# F4_mini.net
KiCad netlist of a schematic drawn in EAGLE
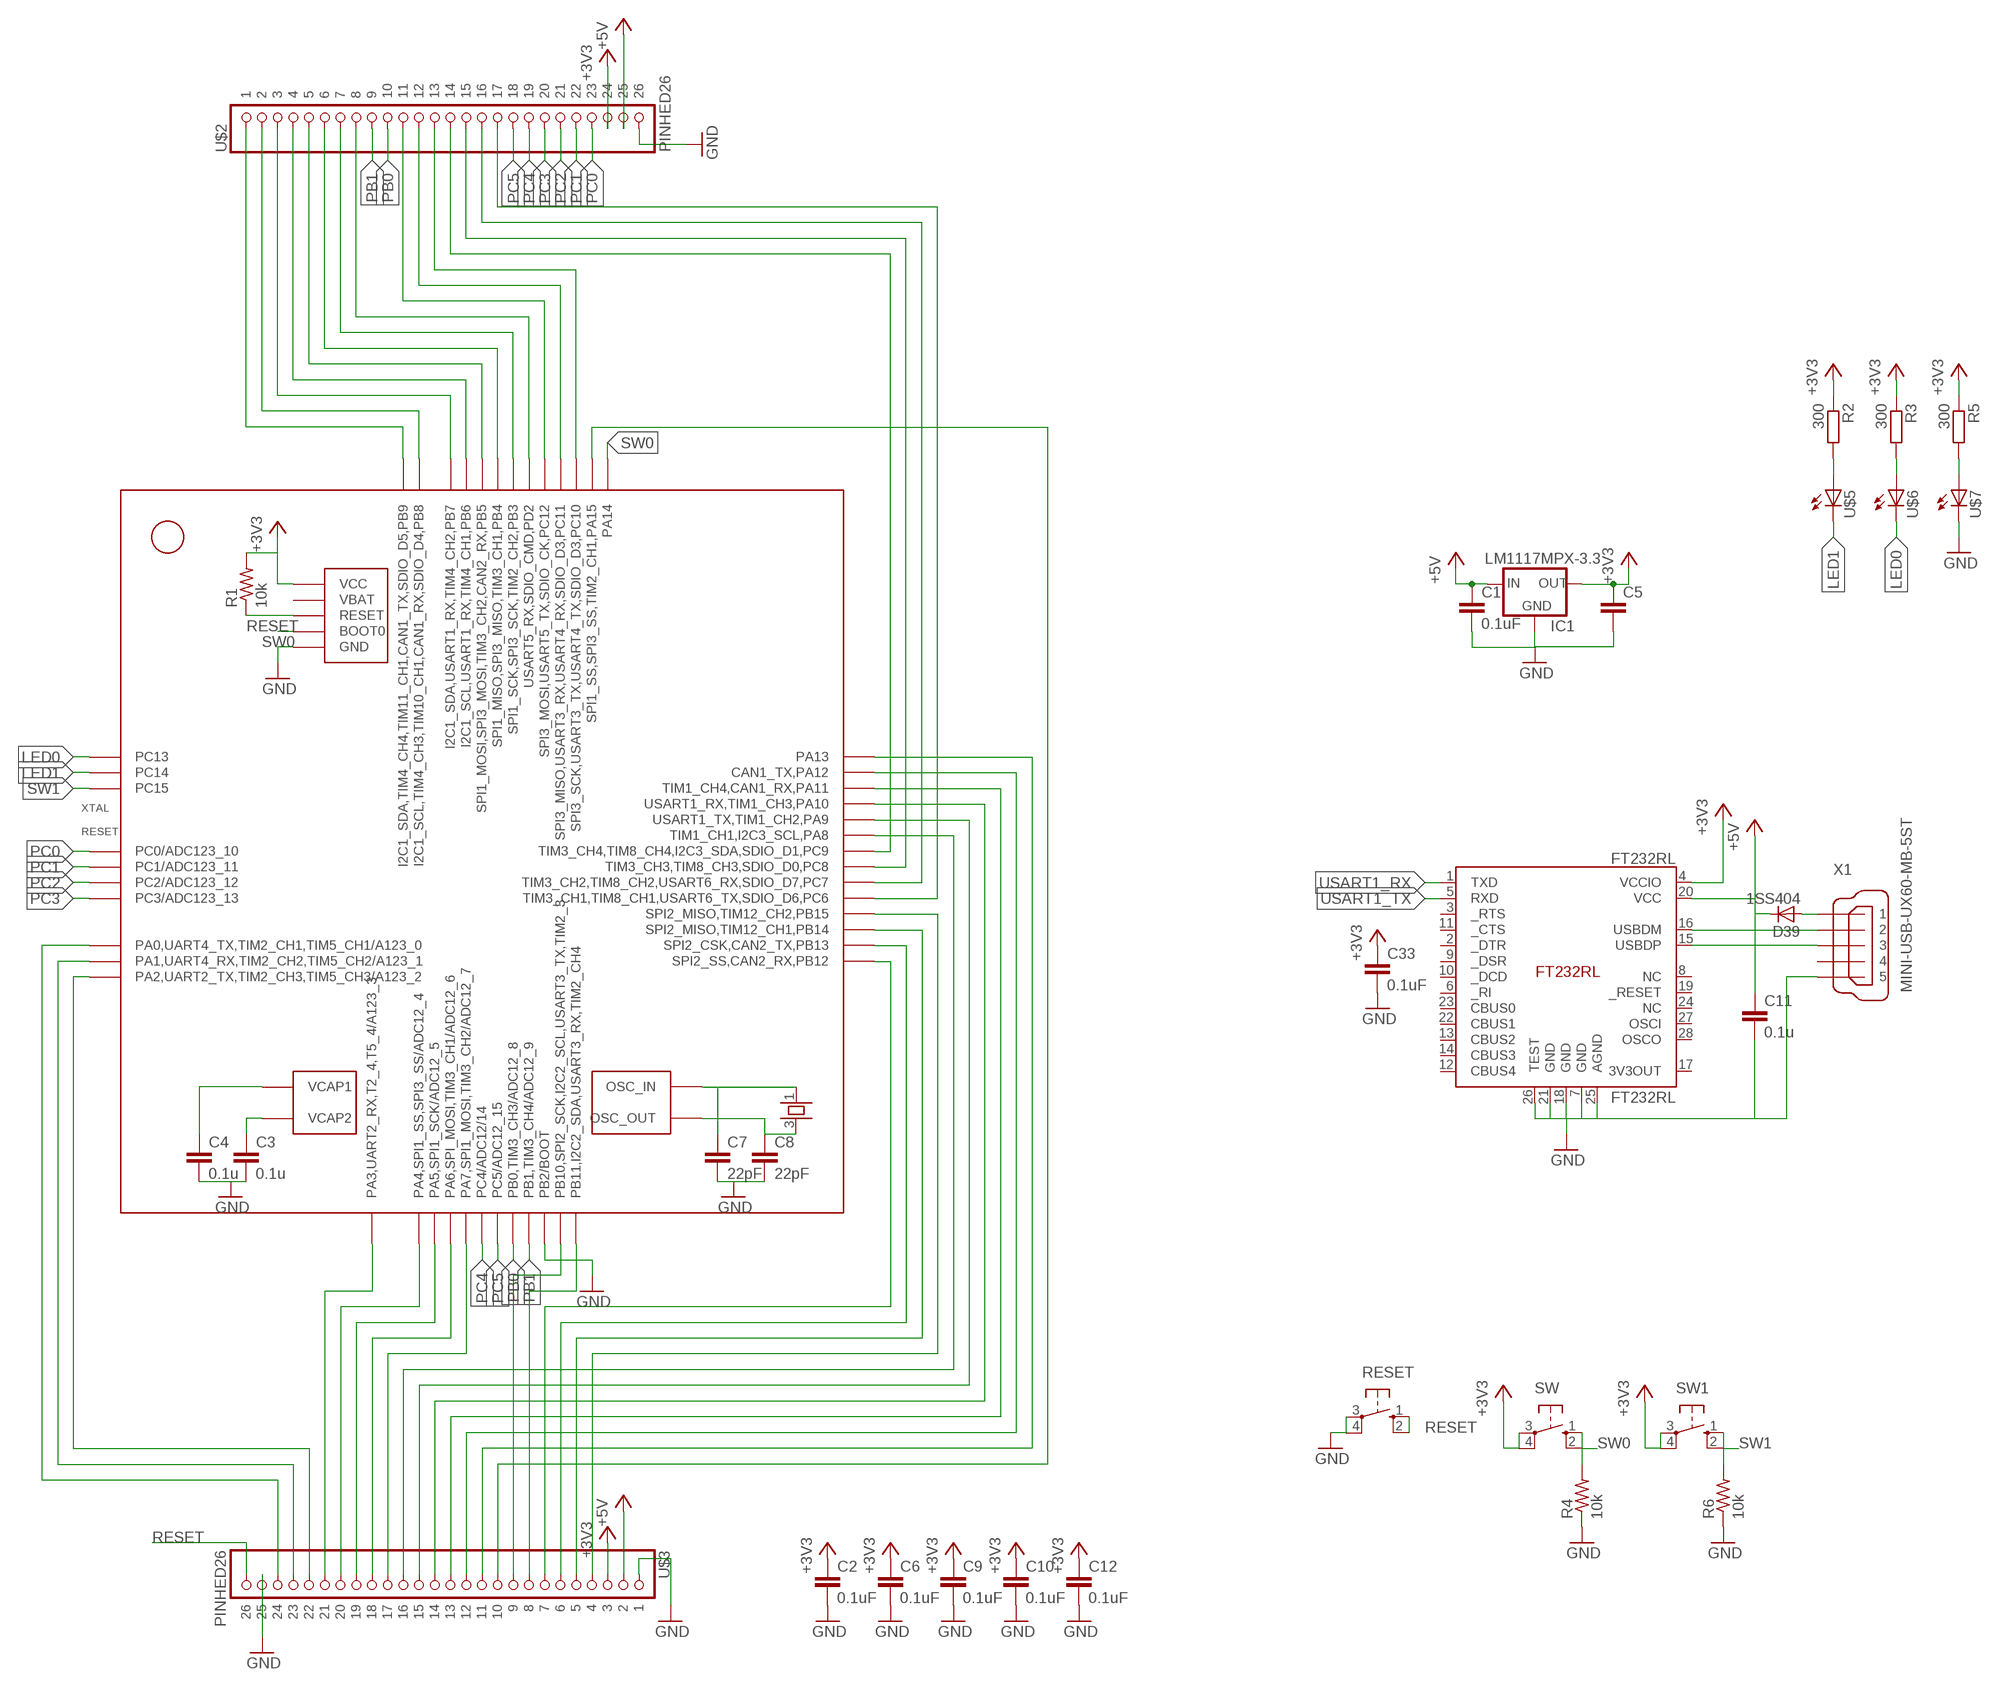
[diagram p0: schematic, sheet 1]

(export (version "E")
  (design (tool "Eeschema 10.0.6"))
  (components
    (comp (ref "C1")
      (value "0.1uF")
      (footprint "eagle-import:C0603K")
      (libsource (lib "eagle-import") (part "C-EUC0603K"))
    )
    (comp (ref "C2")
      (value "0.1uF")
      (footprint "eagle-import:C0603")
      (libsource (lib "eagle-import") (part "C-EUC0603"))
    )
    (comp (ref "C3")
      (value "0.1u")
      (footprint "eagle-import:C0603K")
      (libsource (lib "eagle-import") (part "C-EUC0603K"))
    )
    (comp (ref "C4")
      (value "0.1u")
      (footprint "eagle-import:C0603K")
      (libsource (lib "eagle-import") (part "C-EUC0603K"))
    )
    (comp (ref "C5")
      (value "C-EUC0603K")
      (footprint "eagle-import:C0603K")
      (libsource (lib "eagle-import") (part "C-EUC0603K"))
    )
    (comp (ref "C6")
      (value "0.1uF")
      (footprint "eagle-import:C0603")
      (libsource (lib "eagle-import") (part "C-EUC0603"))
    )
    (comp (ref "C7")
      (value "22pF")
      (footprint "eagle-import:C0603K")
      (libsource (lib "eagle-import") (part "C-EUC0603K"))
    )
    (comp (ref "C8")
      (value "22pF")
      (footprint "eagle-import:C0603K")
      (libsource (lib "eagle-import") (part "C-EUC0603K"))
    )
    (comp (ref "C9")
      (value "0.1uF")
      (footprint "eagle-import:C0603")
      (libsource (lib "eagle-import") (part "C-EUC0603"))
    )
    (comp (ref "C10")
      (value "0.1uF")
      (footprint "eagle-import:C0603")
      (libsource (lib "eagle-import") (part "C-EUC0603"))
    )
    (comp (ref "C11")
      (value "0.1u")
      (footprint "eagle-import:C0603K")
      (libsource (lib "eagle-import") (part "C-EUC0603K"))
    )
    (comp (ref "C12")
      (value "0.1uF")
      (footprint "eagle-import:C0603")
      (libsource (lib "eagle-import") (part "C-EUC0603"))
    )
    (comp (ref "C33")
      (value "0.1uF")
      (footprint "eagle-import:C0603")
      (libsource (lib "eagle-import") (part "C-EUC0603"))
    )
    (comp (ref "D39")
      (value "1SS404")
      (footprint "eagle-import:USC(1.25X2.5)")
      (libsource (lib "eagle-import") (part "1SS404"))
    )
    (comp (ref "FT232RL")
      (value "FT232RL")
      (footprint "eagle-import:SSOP-28")
      (libsource (lib "eagle-import") (part "FT232RL"))
    )
    (comp (ref "IC1")
      (value "LM1117MPX-3.3")
      (footprint "eagle-import:SOT223")
      (libsource (lib "eagle-import") (part "LM1117"))
    )
    (comp (ref "R1")
      (value "10k")
      (footprint "eagle-import:R0603")
      (libsource (lib "eagle-import") (part "R-US_R0603"))
    )
    (comp (ref "R2")
      (value "300")
      (footprint "eagle-import:R0603")
      (libsource (lib "eagle-import") (part "R-EU_R0603"))
    )
    (comp (ref "R3")
      (value "300")
      (footprint "eagle-import:R0603")
      (libsource (lib "eagle-import") (part "R-EU_R0603"))
    )
    (comp (ref "R4")
      (value "10k")
      (footprint "eagle-import:R0603")
      (libsource (lib "eagle-import") (part "R-US_R0603"))
    )
    (comp (ref "R5")
      (value "300")
      (footprint "eagle-import:R0603")
      (libsource (lib "eagle-import") (part "R-EU_R0603"))
    )
    (comp (ref "R6")
      (value "10k")
      (footprint "eagle-import:R0603")
      (libsource (lib "eagle-import") (part "R-US_R0603"))
    )
    (comp (ref "RESET")
      (value "10-XX")
      (footprint "eagle-import:B3F-10XX")
      (fields (field (name "MPN") "B3F-1000"))
      (libsource (lib "eagle-import") (part "10-XX"))
    )
    (comp (ref "SW")
      (value "10-XX")
      (footprint "eagle-import:B3F-10XX")
      (fields (field (name "MPN") "B3F-1000"))
      (libsource (lib "eagle-import") (part "10-XX"))
    )
    (comp (ref "SW1")
      (value "10-XX")
      (footprint "eagle-import:B3F-10XX")
      (fields (field (name "MPN") "B3F-1000"))
      (libsource (lib "eagle-import") (part "10-XX"))
    )
    (comp (ref "U$1")
      (value "STM32F405_T")
      (footprint "eagle-import:LQFP64")
      (libsource (lib "eagle-import") (part "STM32F405_T"))
    )
    (comp (ref "U$2")
      (value "PINHED26")
      (footprint "eagle-import:PINHED26")
      (libsource (lib "eagle-import") (part "PINHED26"))
    )
    (comp (ref "U$3")
      (value "PINHED26")
      (footprint "eagle-import:PINHED26")
      (libsource (lib "eagle-import") (part "PINHED26"))
    )
    (comp (ref "U$4")
      (value "25MHz")
      (footprint "eagle-import:ASF")
      (libsource (lib "eagle-import") (part "ASF_T"))
    )
    (comp (ref "U$5")
      (value "0603")
      (footprint "eagle-import:0603")
      (libsource (lib "eagle-import") (part "0603"))
    )
    (comp (ref "U$6")
      (value "0603")
      (footprint "eagle-import:0603")
      (libsource (lib "eagle-import") (part "0603"))
    )
    (comp (ref "U$7")
      (value "0603")
      (footprint "eagle-import:0603")
      (libsource (lib "eagle-import") (part "0603"))
    )
    (comp (ref "X1")
      (value "MINI-USB-UX60-MB-5ST")
      (footprint "eagle-import:UX60-MB-5ST")
      (libsource (lib "eagle-import") (part "MINI-USB-UX60-MB-5ST"))
    )
  )
  (nets
    (net (code "1") (name "+3V3") (class "Default")
      (node (ref "C10") (pin "1") (pinfunction "1_1") (pintype "passive"))
      (node (ref "C12") (pin "1") (pinfunction "1_1") (pintype "passive"))
      (node (ref "C2") (pin "1") (pinfunction "1_1") (pintype "passive"))
      (node (ref "C33") (pin "1") (pinfunction "1_1") (pintype "passive"))
      (node (ref "C5") (pin "1") (pinfunction "1_1") (pintype "passive"))
      (node (ref "C6") (pin "1") (pinfunction "1_1") (pintype "passive"))
      (node (ref "C9") (pin "1") (pinfunction "1_1") (pintype "passive"))
      (node (ref "FT232RL") (pin "4") (pinfunction "VCCIO_4") (pintype "power_in"))
      (node (ref "IC1") (pin "2") (pinfunction "OUT1_2") (pintype "passive"))
      (node (ref "IC1") (pin "4") (pinfunction "OUT_4") (pintype "passive"))
      (node (ref "R1") (pin "2") (pinfunction "2_2") (pintype "passive"))
      (node (ref "R2") (pin "1") (pinfunction "1_1") (pintype "passive"))
      (node (ref "R3") (pin "1") (pinfunction "1_1") (pintype "passive"))
      (node (ref "R5") (pin "1") (pinfunction "1_1") (pintype "passive"))
      (node (ref "SW") (pin "3") (pinfunction "P_3") (pintype "passive"))
      (node (ref "SW") (pin "4") (pinfunction "P1_4") (pintype "passive"))
      (node (ref "SW1") (pin "3") (pinfunction "P_3") (pintype "passive"))
      (node (ref "SW1") (pin "4") (pinfunction "P1_4") (pintype "passive"))
      (node (ref "U$1") (pin "13") (pinfunction "VCC_13") (pintype "bidirectional"))
      (node (ref "U$1") (pin "19") (pinfunction "VCC_19") (pintype "bidirectional"))
      (node (ref "U$1") (pin "32") (pinfunction "VCC_32") (pintype "bidirectional"))
      (node (ref "U$1") (pin "48") (pinfunction "VCC_48") (pintype "bidirectional"))
      (node (ref "U$1") (pin "64") (pinfunction "VCC_64") (pintype "bidirectional"))
      (node (ref "U$2") (pin "25") (pinfunction "24_25") (pintype "passive"))
      (node (ref "U$3") (pin "4") (pinfunction "3_4") (pintype "passive"))
    )
    (net (code "2") (name "+5V") (class "Default")
      (node (ref "C1") (pin "1") (pinfunction "1_1") (pintype "passive"))
      (node (ref "C11") (pin "1") (pinfunction "1_1") (pintype "passive"))
      (node (ref "D39") (pin "K") (pinfunction "C_K") (pintype "passive"))
      (node (ref "FT232RL") (pin "20") (pinfunction "VCC_20") (pintype "power_in"))
      (node (ref "IC1") (pin "3") (pinfunction "IN_3") (pintype "input"))
      (node (ref "U$2") (pin "26") (pinfunction "25_26") (pintype "passive"))
      (node (ref "U$3") (pin "3") (pinfunction "2_3") (pintype "passive"))
    )
    (net (code "3") (name "/RESET") (class "Default")
      (node (ref "R1") (pin "1") (pinfunction "1_1") (pintype "passive"))
      (node (ref "RESET") (pin "1") (pinfunction "S_1") (pintype "passive"))
      (node (ref "RESET") (pin "2") (pinfunction "S1_2") (pintype "passive"))
      (node (ref "U$1") (pin "7") (pinfunction "RESET_7") (pintype "bidirectional"))
      (node (ref "U$3") (pin "27") (pinfunction "26_27") (pintype "passive"))
    )
    (net (code "4") (name "GND") (class "Default")
      (node (ref "C1") (pin "2") (pinfunction "2_2") (pintype "passive"))
      (node (ref "C10") (pin "2") (pinfunction "2_2") (pintype "passive"))
      (node (ref "C11") (pin "2") (pinfunction "2_2") (pintype "passive"))
      (node (ref "C12") (pin "2") (pinfunction "2_2") (pintype "passive"))
      (node (ref "C2") (pin "2") (pinfunction "2_2") (pintype "passive"))
      (node (ref "C3") (pin "2") (pinfunction "2_2") (pintype "passive"))
      (node (ref "C33") (pin "2") (pinfunction "2_2") (pintype "passive"))
      (node (ref "C4") (pin "2") (pinfunction "2_2") (pintype "passive"))
      (node (ref "C5") (pin "2") (pinfunction "2_2") (pintype "passive"))
      (node (ref "C6") (pin "2") (pinfunction "2_2") (pintype "passive"))
      (node (ref "C7") (pin "2") (pinfunction "2_2") (pintype "passive"))
      (node (ref "C8") (pin "2") (pinfunction "2_2") (pintype "passive"))
      (node (ref "C9") (pin "2") (pinfunction "2_2") (pintype "passive"))
      (node (ref "FT232RL") (pin "18") (pinfunction "GND_18") (pintype "power_in"))
      (node (ref "FT232RL") (pin "21") (pinfunction "GND_21") (pintype "power_in"))
      (node (ref "FT232RL") (pin "25") (pinfunction "AGND_25") (pintype "power_in"))
      (node (ref "FT232RL") (pin "26") (pinfunction "TEST_26") (pintype "bidirectional"))
      (node (ref "FT232RL") (pin "7") (pinfunction "GND_7") (pintype "power_in"))
      (node (ref "IC1") (pin "1") (pinfunction "GND_1") (pintype "input"))
      (node (ref "R4") (pin "1") (pinfunction "1_1") (pintype "passive"))
      (node (ref "R6") (pin "1") (pinfunction "1_1") (pintype "passive"))
      (node (ref "RESET") (pin "3") (pinfunction "P_3") (pintype "passive"))
      (node (ref "RESET") (pin "4") (pinfunction "P1_4") (pintype "passive"))
      (node (ref "U$1") (pin "12") (pinfunction "GND_12") (pintype "bidirectional"))
      (node (ref "U$1") (pin "18") (pinfunction "GND_18") (pintype "bidirectional"))
      (node (ref "U$1") (pin "28") (pinfunction "PB2/BOOT_28") (pintype "bidirectional"))
      (node (ref "U$1") (pin "63") (pinfunction "GND_63") (pintype "bidirectional"))
      (node (ref "U$2") (pin "27") (pinfunction "26_27") (pintype "passive"))
      (node (ref "U$3") (pin "2") (pinfunction "1_2") (pintype "passive"))
      (node (ref "U$3") (pin "26") (pinfunction "25_26") (pintype "passive"))
      (node (ref "U$7") (pin "C") (pinfunction "C_C") (pintype "passive"))
      (node (ref "X1") (pin "5") (pinfunction "5_5") (pintype "input"))
    )
    (net (code "5") (name "LED0") (class "Default")
      (node (ref "U$1") (pin "2") (pinfunction "PC13_2") (pintype "bidirectional"))
      (node (ref "U$6") (pin "C") (pinfunction "C_C") (pintype "passive"))
    )
    (net (code "6") (name "LED1") (class "Default")
      (node (ref "U$1") (pin "3") (pinfunction "PC14_3") (pintype "bidirectional"))
      (node (ref "U$5") (pin "C") (pinfunction "C_C") (pintype "passive"))
    )
    (net (code "7") (name "Net-(D39-PadA)") (class "Default")
      (node (ref "D39") (pin "A") (pinfunction "A_A") (pintype "passive"))
      (node (ref "X1") (pin "1") (pinfunction "1_1") (pintype "input"))
    )
    (net (code "8") (name "Net-(FT232RL-USBDM)") (class "Default")
      (node (ref "FT232RL") (pin "16") (pinfunction "USBDM_16") (pintype "bidirectional"))
      (node (ref "X1") (pin "2") (pinfunction "2_2") (pintype "input"))
    )
    (net (code "9") (name "Net-(FT232RL-USBDP)") (class "Default")
      (node (ref "FT232RL") (pin "15") (pinfunction "USBDP_15") (pintype "bidirectional"))
      (node (ref "X1") (pin "3") (pinfunction "3_3") (pintype "input"))
    )
    (net (code "10") (name "Net-(R2-Pad2)") (class "Default")
      (node (ref "R2") (pin "2") (pinfunction "2_2") (pintype "passive"))
      (node (ref "U$5") (pin "A") (pinfunction "A_A") (pintype "passive"))
    )
    (net (code "11") (name "Net-(R3-Pad2)") (class "Default")
      (node (ref "R3") (pin "2") (pinfunction "2_2") (pintype "passive"))
      (node (ref "U$6") (pin "A") (pinfunction "A_A") (pintype "passive"))
    )
    (net (code "12") (name "Net-(R5-Pad2)") (class "Default")
      (node (ref "R5") (pin "2") (pinfunction "2_2") (pintype "passive"))
      (node (ref "U$7") (pin "A") (pinfunction "A_A") (pintype "passive"))
    )
    (net (code "13") (name "Net-(U$1-CAN1_TX,PA12)") (class "Default")
      (node (ref "U$1") (pin "45") (pinfunction "CAN1_TX,PA12_45") (pintype "bidirectional"))
      (node (ref "U$3") (pin "13") (pinfunction "12_13") (pintype "passive"))
    )
    (net (code "14") (name "Net-(U$1-I2C1_SCL,TIM4_CH3,TIM10_CH1,CAN1_RX,SDIO_D4,PB8)") (class "Default")
      (node (ref "U$1") (pin "61") (pinfunction "I2C1_SCL,TIM4_CH3,TIM10_CH1,CAN1_RX,SDIO_D4,PB8_61") (pintype "bidirectional"))
      (node (ref "U$2") (pin "3") (pinfunction "2_3") (pintype "passive"))
    )
    (net (code "15") (name "Net-(U$1-I2C1_SCL,USART1_RX,TIM4_CH1,PB6)") (class "Default")
      (node (ref "U$1") (pin "58") (pinfunction "I2C1_SCL,USART1_RX,TIM4_CH1,PB6_58") (pintype "bidirectional"))
      (node (ref "U$2") (pin "5") (pinfunction "4_5") (pintype "passive"))
    )
    (net (code "16") (name "Net-(U$1-I2C1_SDA,TIM4_CH4,TIM11_CH1,CAN1_TX,SDIO_D5,PB9)") (class "Default")
      (node (ref "U$1") (pin "62") (pinfunction "I2C1_SDA,TIM4_CH4,TIM11_CH1,CAN1_TX,SDIO_D5,PB9_62") (pintype "bidirectional"))
      (node (ref "U$2") (pin "2") (pinfunction "1_2") (pintype "passive"))
    )
    (net (code "17") (name "Net-(U$1-I2C1_SDA,USART1_RX,TIM4_CH2,PB7)") (class "Default")
      (node (ref "U$1") (pin "59") (pinfunction "I2C1_SDA,USART1_RX,TIM4_CH2,PB7_59") (pintype "bidirectional"))
      (node (ref "U$2") (pin "4") (pinfunction "3_4") (pintype "passive"))
    )
    (net (code "18") (name "Net-(U$1-OSC_IN)") (class "Default")
      (node (ref "C7") (pin "1") (pinfunction "1_1") (pintype "passive"))
      (node (ref "U$1") (pin "5") (pinfunction "OSC_IN_5") (pintype "bidirectional"))
      (node (ref "U$4") (pin "1") (pinfunction "P$1_1") (pintype "bidirectional"))
    )
    (net (code "19") (name "Net-(U$1-OSC_OUT)") (class "Default")
      (node (ref "C8") (pin "1") (pinfunction "1_1") (pintype "passive"))
      (node (ref "U$1") (pin "6") (pinfunction "OSC_OUT_6") (pintype "bidirectional"))
      (node (ref "U$4") (pin "3") (pinfunction "P$2_3") (pintype "bidirectional"))
    )
    (net (code "20") (name "Net-(U$1-PA0,UART4_TX,TIM2_CH1,TIM5_CH1{slash}A123_0)") (class "Default")
      (node (ref "U$1") (pin "14") (pinfunction "PA0,UART4_TX,TIM2_CH1,TIM5_CH1/A123_0_14") (pintype "bidirectional"))
      (node (ref "U$3") (pin "25") (pinfunction "24_25") (pintype "passive"))
    )
    (net (code "21") (name "Net-(U$1-PA1,UART4_RX,TIM2_CH2,TIM5_CH2{slash}A123_1)") (class "Default")
      (node (ref "U$1") (pin "15") (pinfunction "PA1,UART4_RX,TIM2_CH2,TIM5_CH2/A123_1_15") (pintype "bidirectional"))
      (node (ref "U$3") (pin "24") (pinfunction "23_24") (pintype "passive"))
    )
    (net (code "22") (name "Net-(U$1-PA2,UART2_TX,TIM2_CH3,TIM5_CH3{slash}A123_2)") (class "Default")
      (node (ref "U$1") (pin "16") (pinfunction "PA2,UART2_TX,TIM2_CH3,TIM5_CH3/A123_2_16") (pintype "bidirectional"))
      (node (ref "U$3") (pin "23") (pinfunction "22_23") (pintype "passive"))
    )
    (net (code "23") (name "Net-(U$1-PA3,UART2_RX,T2_4,T5_4{slash}A123_3)") (class "Default")
      (node (ref "U$1") (pin "17") (pinfunction "PA3,UART2_RX,T2_4,T5_4/A123_3_17") (pintype "bidirectional"))
      (node (ref "U$3") (pin "22") (pinfunction "21_22") (pintype "passive"))
    )
    (net (code "24") (name "Net-(U$1-PA4,SPI1_SS,SPI3_SS{slash}ADC12_4)") (class "Default")
      (node (ref "U$1") (pin "20") (pinfunction "PA4,SPI1_SS,SPI3_SS/ADC12_4_20") (pintype "bidirectional"))
      (node (ref "U$3") (pin "21") (pinfunction "20_21") (pintype "passive"))
    )
    (net (code "25") (name "Net-(U$1-PA5,SPI1_SCK{slash}ADC12_5)") (class "Default")
      (node (ref "U$1") (pin "21") (pinfunction "PA5,SPI1_SCK/ADC12_5_21") (pintype "bidirectional"))
      (node (ref "U$3") (pin "20") (pinfunction "19_20") (pintype "passive"))
    )
    (net (code "26") (name "Net-(U$1-PA6,SPI_MOSI,TIM3_CH1{slash}ADC12_6)") (class "Default")
      (node (ref "U$1") (pin "22") (pinfunction "PA6,SPI_MOSI,TIM3_CH1/ADC12_6_22") (pintype "bidirectional"))
      (node (ref "U$3") (pin "19") (pinfunction "18_19") (pintype "passive"))
    )
    (net (code "27") (name "Net-(U$1-PA7,SPI1_MOSI,TIM3_CH2{slash}ADC12_7)") (class "Default")
      (node (ref "U$1") (pin "23") (pinfunction "PA7,SPI1_MOSI,TIM3_CH2/ADC12_7_23") (pintype "bidirectional"))
      (node (ref "U$3") (pin "18") (pinfunction "17_18") (pintype "passive"))
    )
    (net (code "28") (name "Net-(U$1-PA13)") (class "Default")
      (node (ref "U$1") (pin "46") (pinfunction "PA13_46") (pintype "bidirectional"))
      (node (ref "U$3") (pin "12") (pinfunction "11_12") (pintype "passive"))
    )
    (net (code "29") (name "Net-(U$1-PB10,SPI2_SCK,I2C2_SCL,USART3_TX,TIM2_3)") (class "Default")
      (node (ref "U$1") (pin "29") (pinfunction "PB10,SPI2_SCK,I2C2_SCL,USART3_TX,TIM2_3_29") (pintype "bidirectional"))
      (node (ref "U$3") (pin "10") (pinfunction "9_10") (pintype "passive"))
    )
    (net (code "30") (name "Net-(U$1-PB11,I2C2_SDA,USART3_RX,TIM2_CH4)") (class "Default")
      (node (ref "U$1") (pin "30") (pinfunction "PB11,I2C2_SDA,USART3_RX,TIM2_CH4_30") (pintype "bidirectional"))
      (node (ref "U$3") (pin "9") (pinfunction "8_9") (pintype "passive"))
    )
    (net (code "31") (name "Net-(U$1-SPI1_MISO,SPI3_MISO,TIM3_CH1,PB4)") (class "Default")
      (node (ref "U$1") (pin "56") (pinfunction "SPI1_MISO,SPI3_MISO,TIM3_CH1,PB4_56") (pintype "bidirectional"))
      (node (ref "U$2") (pin "7") (pinfunction "6_7") (pintype "passive"))
    )
    (net (code "32") (name "Net-(U$1-SPI1_MOSI,SPI3_MOSI,TIM3_CH2,CAN2_RX,PB5)") (class "Default")
      (node (ref "U$1") (pin "57") (pinfunction "SPI1_MOSI,SPI3_MOSI,TIM3_CH2,CAN2_RX,PB5_57") (pintype "bidirectional"))
      (node (ref "U$2") (pin "6") (pinfunction "5_6") (pintype "passive"))
    )
    (net (code "33") (name "Net-(U$1-SPI1_SCK,SPI3_SCK,TIM2_CH2,PB3)") (class "Default")
      (node (ref "U$1") (pin "55") (pinfunction "SPI1_SCK,SPI3_SCK,TIM2_CH2,PB3_55") (pintype "bidirectional"))
      (node (ref "U$2") (pin "8") (pinfunction "7_8") (pintype "passive"))
    )
    (net (code "34") (name "Net-(U$1-SPI1_SS,SPI3_SS,TIM2_CH1,PA15)") (class "Default")
      (node (ref "U$1") (pin "50") (pinfunction "SPI1_SS,SPI3_SS,TIM2_CH1,PA15_50") (pintype "bidirectional"))
      (node (ref "U$3") (pin "11") (pinfunction "10_11") (pintype "passive"))
    )
    (net (code "35") (name "Net-(U$1-SPI2_CSK,CAN2_TX,PB13)") (class "Default")
      (node (ref "U$1") (pin "34") (pinfunction "SPI2_CSK,CAN2_TX,PB13_34") (pintype "bidirectional"))
      (node (ref "U$3") (pin "7") (pinfunction "6_7") (pintype "passive"))
    )
    (net (code "36") (name "Net-(U$1-SPI2_MISO,TIM12_CH1,PB14)") (class "Default")
      (node (ref "U$1") (pin "35") (pinfunction "SPI2_MISO,TIM12_CH1,PB14_35") (pintype "bidirectional"))
      (node (ref "U$3") (pin "6") (pinfunction "5_6") (pintype "passive"))
    )
    (net (code "37") (name "Net-(U$1-SPI2_MISO,TIM12_CH2,PB15)") (class "Default")
      (node (ref "U$1") (pin "36") (pinfunction "SPI2_MISO,TIM12_CH2,PB15_36") (pintype "bidirectional"))
      (node (ref "U$3") (pin "5") (pinfunction "4_5") (pintype "passive"))
    )
    (net (code "38") (name "Net-(U$1-SPI2_SS,CAN2_RX,PB12)") (class "Default")
      (node (ref "U$1") (pin "33") (pinfunction "SPI2_SS,CAN2_RX,PB12_33") (pintype "bidirectional"))
      (node (ref "U$3") (pin "8") (pinfunction "7_8") (pintype "passive"))
    )
    (net (code "39") (name "Net-(U$1-SPI3_MISO,USART3_RX,USART4_RX,SDIO_D3,PC11)") (class "Default")
      (node (ref "U$1") (pin "52") (pinfunction "SPI3_MISO,USART3_RX,USART4_RX,SDIO_D3,PC11_52") (pintype "bidirectional"))
      (node (ref "U$2") (pin "13") (pinfunction "12_13") (pintype "passive"))
    )
    (net (code "40") (name "Net-(U$1-SPI3_MOSI,USART5_TX,SDIO_CK,PC12)") (class "Default")
      (node (ref "U$1") (pin "53") (pinfunction "SPI3_MOSI,USART5_TX,SDIO_CK,PC12_53") (pintype "bidirectional"))
      (node (ref "U$2") (pin "12") (pinfunction "11_12") (pintype "passive"))
    )
    (net (code "41") (name "Net-(U$1-SPI3_SCK,USART3_TX,USART4_TX,SDIO_D3,PC10)") (class "Default")
      (node (ref "U$1") (pin "51") (pinfunction "SPI3_SCK,USART3_TX,USART4_TX,SDIO_D3,PC10_51") (pintype "bidirectional"))
      (node (ref "U$2") (pin "14") (pinfunction "13_14") (pintype "passive"))
    )
    (net (code "42") (name "Net-(U$1-TIM1_CH1,I2C3_SCL,PA8)") (class "Default")
      (node (ref "U$1") (pin "41") (pinfunction "TIM1_CH1,I2C3_SCL,PA8_41") (pintype "bidirectional"))
      (node (ref "U$3") (pin "17") (pinfunction "16_17") (pintype "passive"))
    )
    (net (code "43") (name "Net-(U$1-TIM1_CH4,CAN1_RX,PA11)") (class "Default")
      (node (ref "U$1") (pin "44") (pinfunction "TIM1_CH4,CAN1_RX,PA11_44") (pintype "bidirectional"))
      (node (ref "U$3") (pin "14") (pinfunction "13_14") (pintype "passive"))
    )
    (net (code "44") (name "Net-(U$1-TIM3_CH1,TIM8_CH1,USART6_TX,SDIO_D6,PC6)") (class "Default")
      (node (ref "U$1") (pin "37") (pinfunction "TIM3_CH1,TIM8_CH1,USART6_TX,SDIO_D6,PC6_37") (pintype "bidirectional"))
      (node (ref "U$2") (pin "18") (pinfunction "17_18") (pintype "passive"))
    )
    (net (code "45") (name "Net-(U$1-TIM3_CH2,TIM8_CH2,USART6_RX,SDIO_D7,PC7)") (class "Default")
      (node (ref "U$1") (pin "38") (pinfunction "TIM3_CH2,TIM8_CH2,USART6_RX,SDIO_D7,PC7_38") (pintype "bidirectional"))
      (node (ref "U$2") (pin "17") (pinfunction "16_17") (pintype "passive"))
    )
    (net (code "46") (name "Net-(U$1-TIM3_CH3,TIM8_CH3,SDIO_D0,PC8)") (class "Default")
      (node (ref "U$1") (pin "39") (pinfunction "TIM3_CH3,TIM8_CH3,SDIO_D0,PC8_39") (pintype "bidirectional"))
      (node (ref "U$2") (pin "16") (pinfunction "15_16") (pintype "passive"))
    )
    (net (code "47") (name "Net-(U$1-TIM3_CH4,TIM8_CH4,I2C3_SDA,SDIO_D1,PC9)") (class "Default")
      (node (ref "U$1") (pin "40") (pinfunction "TIM3_CH4,TIM8_CH4,I2C3_SDA,SDIO_D1,PC9_40") (pintype "bidirectional"))
      (node (ref "U$2") (pin "15") (pinfunction "14_15") (pintype "passive"))
    )
    (net (code "48") (name "Net-(U$1-USART5_RX,SDIO_CMD,PD2)") (class "Default")
      (node (ref "U$1") (pin "54") (pinfunction "USART5_RX,SDIO_CMD,PD2_54") (pintype "bidirectional"))
      (node (ref "U$2") (pin "9") (pinfunction "8_9") (pintype "passive"))
    )
    (net (code "49") (name "Net-(U$1-VCAP1)") (class "Default")
      (node (ref "C4") (pin "1") (pinfunction "1_1") (pintype "passive"))
      (node (ref "U$1") (pin "31") (pinfunction "VCAP1_31") (pintype "bidirectional"))
    )
    (net (code "50") (name "Net-(U$1-VCAP2)") (class "Default")
      (node (ref "C3") (pin "1") (pinfunction "1_1") (pintype "passive"))
      (node (ref "U$1") (pin "47") (pinfunction "VCAP2_47") (pintype "bidirectional"))
    )
    (net (code "51") (name "PB0") (class "Default")
      (node (ref "U$1") (pin "26") (pinfunction "PB0,TIM3_CH3/ADC12_8_26") (pintype "bidirectional"))
      (node (ref "U$2") (pin "11") (pinfunction "10_11") (pintype "passive"))
    )
    (net (code "52") (name "PB1") (class "Default")
      (node (ref "U$1") (pin "27") (pinfunction "PB1,TIM3_CH4/ADC12_9_27") (pintype "bidirectional"))
      (node (ref "U$2") (pin "10") (pinfunction "9_10") (pintype "passive"))
    )
    (net (code "53") (name "PC0") (class "Default")
      (node (ref "U$1") (pin "8") (pinfunction "PC0/ADC123_10_8") (pintype "bidirectional"))
      (node (ref "U$2") (pin "24") (pinfunction "23_24") (pintype "passive"))
    )
    (net (code "54") (name "PC1") (class "Default")
      (node (ref "U$1") (pin "9") (pinfunction "PC1/ADC123_11_9") (pintype "bidirectional"))
      (node (ref "U$2") (pin "23") (pinfunction "22_23") (pintype "passive"))
    )
    (net (code "55") (name "PC2") (class "Default")
      (node (ref "U$1") (pin "10") (pinfunction "PC2/ADC123_12_10") (pintype "bidirectional"))
      (node (ref "U$2") (pin "22") (pinfunction "21_22") (pintype "passive"))
    )
    (net (code "56") (name "PC3") (class "Default")
      (node (ref "U$1") (pin "11") (pinfunction "PC3/ADC123_13_11") (pintype "bidirectional"))
      (node (ref "U$2") (pin "21") (pinfunction "20_21") (pintype "passive"))
    )
    (net (code "57") (name "PC4") (class "Default")
      (node (ref "U$1") (pin "24") (pinfunction "PC4/ADC12/14_24") (pintype "bidirectional"))
      (node (ref "U$2") (pin "20") (pinfunction "19_20") (pintype "passive"))
    )
    (net (code "58") (name "PC5") (class "Default")
      (node (ref "U$1") (pin "25") (pinfunction "PC5/ADC12_15_25") (pintype "bidirectional"))
      (node (ref "U$2") (pin "19") (pinfunction "18_19") (pintype "passive"))
    )
    (net (code "59") (name "SW0") (class "Default")
      (node (ref "R4") (pin "2") (pinfunction "2_2") (pintype "passive"))
      (node (ref "SW") (pin "1") (pinfunction "S_1") (pintype "passive"))
      (node (ref "SW") (pin "2") (pinfunction "S1_2") (pintype "passive"))
      (node (ref "U$1") (pin "49") (pinfunction "PA14_49") (pintype "bidirectional"))
      (node (ref "U$1") (pin "60") (pinfunction "BOOT0_60") (pintype "bidirectional"))
    )
    (net (code "60") (name "SW1") (class "Default")
      (node (ref "R6") (pin "2") (pinfunction "2_2") (pintype "passive"))
      (node (ref "SW1") (pin "1") (pinfunction "S_1") (pintype "passive"))
      (node (ref "SW1") (pin "2") (pinfunction "S1_2") (pintype "passive"))
      (node (ref "U$1") (pin "4") (pinfunction "PC15_4") (pintype "bidirectional"))
    )
    (net (code "61") (name "USART1_RX") (class "Default")
      (node (ref "FT232RL") (pin "1") (pinfunction "TXD_1") (pintype "output"))
      (node (ref "U$1") (pin "43") (pinfunction "USART1_RX,TIM1_CH3,PA10_43") (pintype "bidirectional"))
      (node (ref "U$3") (pin "15") (pinfunction "14_15") (pintype "passive"))
    )
    (net (code "62") (name "USART1_TX") (class "Default")
      (node (ref "FT232RL") (pin "5") (pinfunction "RXD_5") (pintype "input"))
      (node (ref "U$1") (pin "42") (pinfunction "USART1_TX,TIM1_CH2,PA9_42") (pintype "bidirectional"))
      (node (ref "U$3") (pin "16") (pinfunction "15_16") (pintype "passive"))
    )
    (net (code "63") (name "unconnected-(FT232RL-3V3OUT-Pad17)") (class "Default")
      (node (ref "FT232RL") (pin "17") (pinfunction "3V3OUT_17") (pintype "output"))
    )
    (net (code "64") (name "unconnected-(FT232RL-CBUS0-Pad23)") (class "Default")
      (node (ref "FT232RL") (pin "23") (pinfunction "CBUS0_23") (pintype "bidirectional"))
    )
    (net (code "65") (name "unconnected-(FT232RL-CBUS1-Pad22)") (class "Default")
      (node (ref "FT232RL") (pin "22") (pinfunction "CBUS1_22") (pintype "bidirectional"))
    )
    (net (code "66") (name "unconnected-(FT232RL-CBUS2-Pad13)") (class "Default")
      (node (ref "FT232RL") (pin "13") (pinfunction "CBUS2_13") (pintype "bidirectional"))
    )
    (net (code "67") (name "unconnected-(FT232RL-CBUS3-Pad14)") (class "Default")
      (node (ref "FT232RL") (pin "14") (pinfunction "CBUS3_14") (pintype "bidirectional"))
    )
    (net (code "68") (name "unconnected-(FT232RL-CBUS4-Pad12)") (class "Default")
      (node (ref "FT232RL") (pin "12") (pinfunction "CBUS4_12") (pintype "bidirectional"))
    )
    (net (code "69") (name "unconnected-(FT232RL-NC-Pad8)") (class "Default")
      (node (ref "FT232RL") (pin "8") (pinfunction "NC_8") (pintype "no_connect"))
    )
    (net (code "70") (name "unconnected-(FT232RL-NC-Pad24)") (class "Default")
      (node (ref "FT232RL") (pin "24") (pinfunction "NC_24") (pintype "no_connect"))
    )
    (net (code "71") (name "unconnected-(FT232RL-OSCI-Pad27)") (class "Default")
      (node (ref "FT232RL") (pin "27") (pinfunction "OSCI_27") (pintype "input"))
    )
    (net (code "72") (name "unconnected-(FT232RL-OSCO-Pad28)") (class "Default")
      (node (ref "FT232RL") (pin "28") (pinfunction "OSCO_28") (pintype "output"))
    )
    (net (code "73") (name "unconnected-(FT232RL-_CTS-Pad11)") (class "Default")
      (node (ref "FT232RL") (pin "11") (pinfunction "_CTS_11") (pintype "input"))
    )
    (net (code "74") (name "unconnected-(FT232RL-_DCD-Pad10)") (class "Default")
      (node (ref "FT232RL") (pin "10") (pinfunction "_DCD_10") (pintype "input"))
    )
    (net (code "75") (name "unconnected-(FT232RL-_DSR-Pad9)") (class "Default")
      (node (ref "FT232RL") (pin "9") (pinfunction "_DSR_9") (pintype "input"))
    )
    (net (code "76") (name "unconnected-(FT232RL-_DTR-Pad2)") (class "Default")
      (node (ref "FT232RL") (pin "2") (pinfunction "_DTR_2") (pintype "input"))
    )
    (net (code "77") (name "unconnected-(FT232RL-_RESET-Pad19)") (class "Default")
      (node (ref "FT232RL") (pin "19") (pinfunction "_RESET_19") (pintype "input"))
    )
    (net (code "78") (name "unconnected-(FT232RL-_RI-Pad6)") (class "Default")
      (node (ref "FT232RL") (pin "6") (pinfunction "_RI_6") (pintype "input"))
    )
    (net (code "79") (name "unconnected-(FT232RL-_RTS-Pad3)") (class "Default")
      (node (ref "FT232RL") (pin "3") (pinfunction "_RTS_3") (pintype "output"))
    )
    (net (code "80") (name "unconnected-(U$1-VBAT-Pad1)") (class "Default")
      (node (ref "U$1") (pin "1") (pinfunction "VBAT_1") (pintype "bidirectional"))
    )
    (net (code "81") (name "unconnected-(X1-Pad4)") (class "Default")
      (node (ref "X1") (pin "4") (pinfunction "4_4") (pintype "input"))
    )
  )
)
